# Power_Regulators_Digital_4.net
KiCad netlist of a schematic drawn in Altium Designer
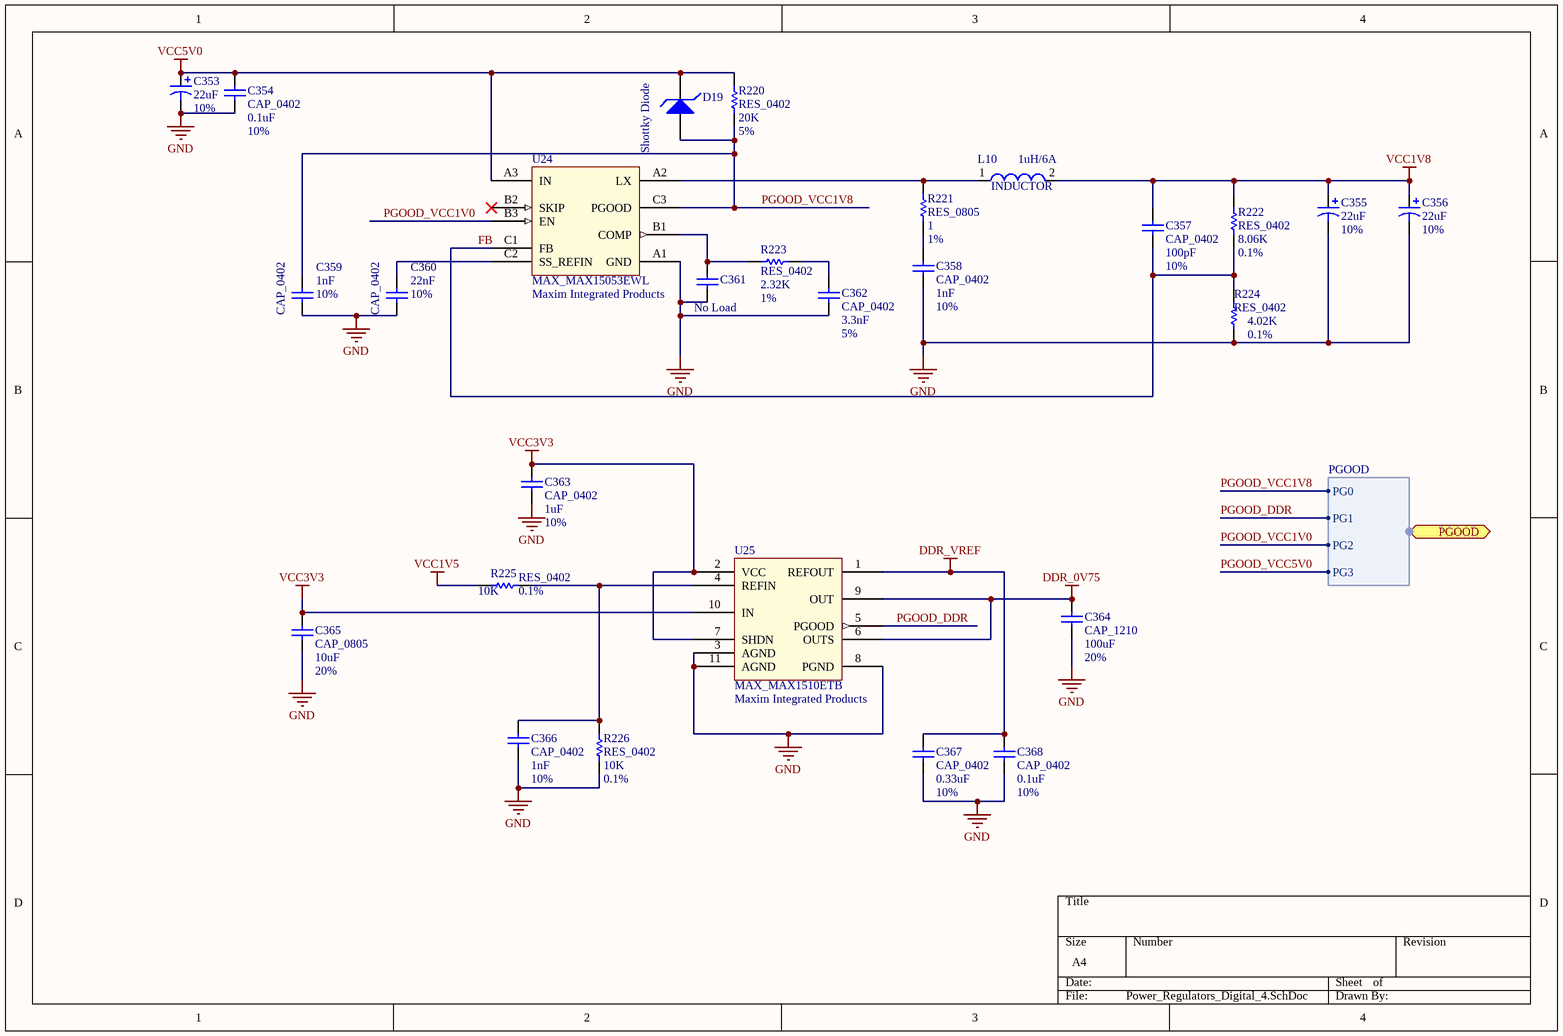
[diagram p0: Power_Regulators_Digital_4.SchDoc]

(export (version "E")
  (design (tool "Eeschema 10.0.6"))
  (components
    (comp (ref "C353")
      (value "22uF")
      (footprint "Polarized_CAPC1210(3225)")
      (description "22uF, tantalum, 10% 6.3V, 1210")
      (fields
        (field (name "TOLERANCE") "10%")
        (field (name "PART NUMBER") "TAJB226K006RNJ")
        (field (name "MANUFACTURER") "AVX Corporation")
      )
      (libsource (lib "COMRAD_Database") (part "Cap Pol1"))
    )
    (comp (ref "C354")
      (value "CAP_0402")
      (footprint "CAPC0402(1005)60_N")
      (description "0.1uf, ceramic, 10%, 6.3V, X5R, 0402")
      (fields
        (field (name "ALTIUM_VALUE") "0.1uF")
        (field (name "TOLERANCE") "10%")
        (field (name "PART NUMBER") "C1005X5R0J104K")
        (field (name "MANUFACTURER") "TDK Corporation")
      )
      (libsource (lib "COMRAD_Database") (part "CAP_0402"))
    )
    (comp (ref "C355")
      (value "22uF")
      (footprint "Polarized_CAPC1210(3225)")
      (description "22uF, tantalum, 10% 6.3V, 1210")
      (fields
        (field (name "TOLERANCE") "10%")
        (field (name "PART NUMBER") "TAJB226K006RNJ")
        (field (name "MANUFACTURER") "AVX Corporation")
      )
      (libsource (lib "COMRAD_Database") (part "Cap Pol1"))
    )
    (comp (ref "C356")
      (value "22uF")
      (footprint "Polarized_CAPC1210(3225)")
      (description "22uF, tantalum, 10% 6.3V, 1210")
      (fields
        (field (name "TOLERANCE") "10%")
        (field (name "PART NUMBER") "TAJB226K006RNJ")
        (field (name "MANUFACTURER") "AVX Corporation")
      )
      (libsource (lib "COMRAD_Database") (part "Cap Pol1"))
    )
    (comp (ref "C357")
      (value "CAP_0402")
      (footprint "CAPC0402(1005)60_N")
      (description "100pF, ceramic, 10% 6.3V X7R, 0402")
      (fields
        (field (name "ALTIUM_VALUE") "100pF")
        (field (name "TOLERANCE") "10%")
        (field (name "PART NUMBER") "04026C101KAT2A")
        (field (name "MANUFACTURER") "AVX Corporation")
      )
      (libsource (lib "COMRAD_Database") (part "CAP_0402"))
    )
    (comp (ref "C358")
      (value "CAP_0402")
      (footprint "CAPC0402(1005)60_N")
      (description "1000pF, ceramic, 10% 25V X7R, 0402")
      (fields
        (field (name "ALTIUM_VALUE") "1nF")
        (field (name "TOLERANCE") "10%")
        (field (name "PART NUMBER") "ECJ-0EB1E102K")
        (field (name "MANUFACTURER") "Panasonic - ECG")
      )
      (libsource (lib "COMRAD_Database") (part "CAP_0402"))
    )
    (comp (ref "C359")
      (value "CAP_0402")
      (footprint "CAPC0402(1005)60_N")
      (description "1000pF, ceramic, 10% 25V X7R, 0402")
      (fields
        (field (name "ALTIUM_VALUE") "1nF")
        (field (name "TOLERANCE") "10%")
        (field (name "PART NUMBER") "ECJ-0EB1E102K")
        (field (name "MANUFACTURER") "Panasonic - ECG")
      )
      (libsource (lib "COMRAD_Database") (part "CAP_0402"))
    )
    (comp (ref "C360")
      (value "CAP_0402")
      (footprint "CAPC0402(1005)60_N")
      (description "0.022uF, ceramic, 10%, 16V, X7R, 0402")
      (fields
        (field (name "ALTIUM_VALUE") "22nF")
        (field (name "TOLERANCE") "10%")
        (field (name "PART NUMBER") "0402YC223KAT2A")
        (field (name "MANUFACTURER") "AVX Corporation")
      )
      (libsource (lib "COMRAD_Database") (part "CAP_0402"))
    )
    (comp (ref "C361")
      (value "No Load")
      (footprint "CAPC0201(0603)33_N:CAPC0201(0603)33_N")
      (description "Generic Capacitor")
      (fields (field (name "Comment") "CAP_0201"))
      (libsource (lib "COMRAD_Database") (part "CAP_0201"))
    )
    (comp (ref "C362")
      (value "CAP_0402")
      (footprint "CAPC0402(1005)60_N")
      (description "3300pF, ceramic 5% 10V, 0402")
      (fields
        (field (name "ALTIUM_VALUE") "3.3nF")
        (field (name "TOLERANCE") "5%")
        (field (name "PART NUMBER") "LMK105SD332JV-F")
        (field (name "MANUFACTURER") "Taiyo Yuden")
      )
      (libsource (lib "COMRAD_Database") (part "CAP_0402"))
    )
    (comp (ref "C363")
      (value "CAP_0402")
      (footprint "CAPC0402(1005)60_N")
      (description "1uF, ceramic, 10%, 6.3V, X5R, 0402")
      (fields
        (field (name "ALTIUM_VALUE") "1uF")
        (field (name "TOLERANCE") "10%")
        (field (name "PART NUMBER") "C1005X5R0J105K")
        (field (name "MANUFACTURER") "TDK Corporation")
      )
      (libsource (lib "COMRAD_Database") (part "CAP_0402"))
    )
    (comp (ref "C364")
      (value "CAP_1210")
      (footprint "CAPC1210(3225)100_N")
      (description "100uF, ceramic, 20% 6.3V X5R, 1210")
      (fields
        (field (name "ALTIUM_VALUE") "100uF")
        (field (name "TOLERANCE") "20%")
        (field (name "PART NUMBER") "GRM32ER60J107ME20L")
        (field (name "MANUFACTURER") "Murata Electronics North America")
      )
      (libsource (lib "COMRAD_Database") (part "CAP_1210"))
    )
    (comp (ref "C365")
      (value "CAP_0805")
      (footprint "CAPC0805(2012)75_N")
      (description "10uF, ceramic, 20%, 6.3V, X5R 0805")
      (fields
        (field (name "ALTIUM_VALUE") "10uF")
        (field (name "TOLERANCE") "20%")
        (field (name "PART NUMBER") "ECJ-2FB0J106M")
        (field (name "MANUFACTURER") "Panasonic - ECG")
      )
      (libsource (lib "COMRAD_Database") (part "CAP_0805"))
    )
    (comp (ref "C366")
      (value "CAP_0402")
      (footprint "CAPC0402(1005)60_N")
      (description "1000pF, ceramic, 10% 25V X7R, 0402")
      (fields
        (field (name "ALTIUM_VALUE") "1nF")
        (field (name "TOLERANCE") "10%")
        (field (name "PART NUMBER") "ECJ-0EB1E102K")
        (field (name "MANUFACTURER") "Panasonic - ECG")
      )
      (libsource (lib "COMRAD_Database") (part "CAP_0402"))
    )
    (comp (ref "C367")
      (value "CAP_0402")
      (footprint "CAPC0402(1005)60_N")
      (description "0.33uF, ceramic, 10% 16V X5R, 0402")
      (fields
        (field (name "ALTIUM_VALUE") "0.33uF")
        (field (name "TOLERANCE") "10%")
        (field (name "PART NUMBER") "C1005X5R1C334K")
        (field (name "MANUFACTURER") "TDK Corporation")
      )
      (libsource (lib "COMRAD_Database") (part "CAP_0402"))
    )
    (comp (ref "C368")
      (value "CAP_0402")
      (footprint "CAPC0402(1005)60_N")
      (description "0.1uf, ceramic, 10%, 6.3V, X5R, 0402")
      (fields
        (field (name "ALTIUM_VALUE") "0.1uF")
        (field (name "TOLERANCE") "10%")
        (field (name "PART NUMBER") "C1005X5R0J104K")
        (field (name "MANUFACTURER") "TDK Corporation")
      )
      (libsource (lib "COMRAD_Database") (part "CAP_0402"))
    )
    (comp (ref "D19")
      (value "Shottky Diode")
      (footprint "SchottkyDiode_RB751S40_2-PIN")
      (description "RB751S40, 40V 30mA schottky, SOD523F")
      (fields (field (name "PART NUMBER") "RB751S40") (field (name "MANUFACTURER") "FAIRCHILD SEMICONDUCTOR"))
      (libsource (lib "COMRAD_Database") (part "ShottkyDiode"))
    )
    (comp (ref "L10")
      (value "INDUCTOR")
      (footprint "Inductor_SRN6045-Series_2-PIN")
      (description "SRN6045-1R0Y, 1uH 4.2A-8.5A, CDRH6D38")
      (fields
        (field (name "ALTIUM_VALUE") "1uH/6A")
        (field (name "PART NUMBER") "SRN6045-1R0Y")
        (field (name "MANUFACTURER") "Bourns")
      )
      (libsource (lib "COMRAD_Database") (part "INDUCTOR"))
    )
    (comp (ref "R220")
      (value "RES_0402")
      (footprint "RESC0402(1005)_N")
      (description "20K ohm, 5%, 1/16W, 0402")
      (fields
        (field (name "ALTIUM_VALUE") "20K")
        (field (name "TOLERANCE") "5%")
        (field (name "PART NUMBER") "ERJ-2GEJ203X")
        (field (name "MANUFACTURER") "Panasonic - ECG")
      )
      (libsource (lib "COMRAD_Database") (part "RES_0402"))
    )
    (comp (ref "R221")
      (value "RES_0805")
      (footprint "RESC0805(2012)_N")
      (description "1 ohm, 1% 1/4W, 0805")
      (fields
        (field (name "ALTIUM_VALUE") "1")
        (field (name "TOLERANCE") "1%")
        (field (name "PART NUMBER") "MCR10EZHFL1R00")
        (field (name "MANUFACTURER") "ROHM")
      )
      (libsource (lib "COMRAD_Database") (part "RES_0805"))
    )
    (comp (ref "R222")
      (value "RES_0402")
      (footprint "RESC0402(1005)_N")
      (description "8.06K ohm, 0.1% 1/16W, 0402")
      (fields
        (field (name "ALTIUM_VALUE") "8.06K")
        (field (name "TOLERANCE") "0.1%")
        (field (name "PART NUMBER") "2-1879215-9")
        (field (name "MANUFACTURER") "TE Connectivity")
      )
      (libsource (lib "COMRAD_Database") (part "RES_0402"))
    )
    (comp (ref "R223")
      (value "RES_0402")
      (footprint "RESC0402(1005)_N")
      (description "2.32K ohm, 1% 1/16W, 0402")
      (fields
        (field (name "ALTIUM_VALUE") "2.32K")
        (field (name "TOLERANCE") "1%")
        (field (name "PART NUMBER") "ERJ-2RKF2321X")
        (field (name "MANUFACTURER") "Panasonic - ECG")
      )
      (libsource (lib "COMRAD_Database") (part "RES_0402"))
    )
    (comp (ref "R224")
      (value "RES_0402")
      (footprint "RESC0402(1005)_N")
      (description "4.02K ohm, 0.1% 1/16W, 0402")
      (fields
        (field (name "ALTIUM_VALUE") "4.02K")
        (field (name "TOLERANCE") "0.1%")
        (field (name "PART NUMBER") "RG1005P-4021-B-T5")
        (field (name "MANUFACTURER") "Susumu Co Ltd")
      )
      (libsource (lib "COMRAD_Database") (part "RES_0402"))
    )
    (comp (ref "R225")
      (value "RES_0402")
      (footprint "RESC0402(1005)_N")
      (description "10K ohm, 0.1% 1/16W, 0402")
      (fields
        (field (name "ALTIUM_VALUE") "10K")
        (field (name "TOLERANCE") "0.1%")
        (field (name "PART NUMBER") "ERA-2AEB103X")
        (field (name "MANUFACTURER") "Panasonic - ECG")
      )
      (libsource (lib "COMRAD_Database") (part "RES_0402"))
    )
    (comp (ref "R226")
      (value "RES_0402")
      (footprint "RESC0402(1005)_N")
      (description "10K ohm, 0.1% 1/16W, 0402")
      (fields
        (field (name "ALTIUM_VALUE") "10K")
        (field (name "TOLERANCE") "0.1%")
        (field (name "PART NUMBER") "ERA-2AEB103X")
        (field (name "MANUFACTURER") "Panasonic - ECG")
      )
      (libsource (lib "COMRAD_Database") (part "RES_0402"))
    )
    (comp (ref "U24")
      (value "MAX_MAX15053EWL")
      (footprint "MAX_MAX15053EWL_9WLP_W91E1Z+1")
      (description "MAX15053EWL, 2A, Current-Mode Synchronous, Step-Down reg, WLP9")
      (fields
        (field (name "PART NUMBER") "MAX15053EWL+T")
        (field (name "MANUFACTURER") "Maxim Integrated Products")
      )
      (libsource (lib "COMRAD_Database") (part "MAX_MAX15053EWL"))
    )
    (comp (ref "U25")
      (value "MAX_MAX1510ETB")
      (footprint "MAX_MAX1510ETB_10TDFN_T1033+1")
      (description "MAX1510ETB, Low-Voltage, DDR Linear Regulators, DFN10")
      (fields
        (field (name "PART NUMBER") "MAX1510ETB+T")
        (field (name "MANUFACTURER") "Maxim Integrated Products")
      )
      (libsource (lib "COMRAD_Database") (part "MAX_MAX1510ETB"))
    )
  )
  (nets
    (net (code "2") (name "/FB") (class "Default")
      (node (ref "C357") (pin "1") (pinfunction "1_1") (pintype "passive"))
      (node (ref "R222") (pin "1") (pinfunction "1_1") (pintype "passive"))
      (node (ref "R224") (pin "2") (pinfunction "2_2") (pintype "passive"))
      (node (ref "U24") (pin "C1") (pinfunction "FB_C1") (pintype "power_in"))
    )
    (net (code "3") (name "/PGOOD_DDR") (class "Default")
      (node (ref "U25") (pin "5") (pinfunction "PGOOD_5") (pintype "output"))
    )
    (net (code "4") (name "/PGOOD_VCC1V0") (class "Default")
      (node (ref "U24") (pin "B3") (pinfunction "EN_B3") (pintype "input"))
    )
    (net (code "5") (name "/PGOOD_VCC1V8") (class "Default")
      (node (ref "C359") (pin "2") (pinfunction "2_2") (pintype "passive"))
      (node (ref "D19") (pin "2") (pinfunction "A_2") (pintype "passive"))
      (node (ref "R220") (pin "1") (pinfunction "1_1") (pintype "passive"))
      (node (ref "U24") (pin "C3") (pinfunction "PGOOD_C3") (pintype "passive"))
    )
    (net (code "8") (name "DDR_0V75") (class "Default")
      (node (ref "C364") (pin "2") (pinfunction "2_2") (pintype "passive"))
      (node (ref "U25") (pin "6") (pinfunction "OUTS_6") (pintype "passive"))
      (node (ref "U25") (pin "9") (pinfunction "OUT_9") (pintype "passive"))
    )
    (net (code "9") (name "DDR_VREF") (class "Default")
      (node (ref "C367") (pin "2") (pinfunction "2_2") (pintype "passive"))
      (node (ref "C368") (pin "2") (pinfunction "2_2") (pintype "passive"))
      (node (ref "U25") (pin "1") (pinfunction "REFOUT_1") (pintype "power_in"))
    )
    (net (code "10") (name "GND") (class "Default")
      (node (ref "C353") (pin "2") (pinfunction "2_2") (pintype "passive"))
      (node (ref "C354") (pin "1") (pinfunction "1_1") (pintype "passive"))
      (node (ref "C355") (pin "2") (pinfunction "2_2") (pintype "passive"))
      (node (ref "C356") (pin "2") (pinfunction "2_2") (pintype "passive"))
      (node (ref "C358") (pin "1") (pinfunction "1_1") (pintype "passive"))
      (node (ref "C359") (pin "1") (pinfunction "1_1") (pintype "passive"))
      (node (ref "C360") (pin "1") (pinfunction "1_1") (pintype "passive"))
      (node (ref "C361") (pin "1") (pinfunction "1_1") (pintype "passive"))
      (node (ref "C362") (pin "1") (pinfunction "1_1") (pintype "passive"))
      (node (ref "C363") (pin "1") (pinfunction "1_1") (pintype "passive"))
      (node (ref "C364") (pin "1") (pinfunction "1_1") (pintype "passive"))
      (node (ref "C365") (pin "1") (pinfunction "1_1") (pintype "passive"))
      (node (ref "C366") (pin "1") (pinfunction "1_1") (pintype "passive"))
      (node (ref "C367") (pin "1") (pinfunction "1_1") (pintype "passive"))
      (node (ref "C368") (pin "1") (pinfunction "1_1") (pintype "passive"))
      (node (ref "R224") (pin "1") (pinfunction "1_1") (pintype "passive"))
      (node (ref "R226") (pin "1") (pinfunction "1_1") (pintype "passive"))
      (node (ref "U24") (pin "A1") (pinfunction "GND_A1") (pintype "power_in"))
      (node (ref "U25") (pin "11") (pinfunction "AGND_11") (pintype "power_in"))
      (node (ref "U25") (pin "3") (pinfunction "AGND_3") (pintype "power_in"))
      (node (ref "U25") (pin "8") (pinfunction "PGND_8") (pintype "power_in"))
    )
    (net (code "11") (name "Net-(C358-Pad2)") (class "Default")
      (node (ref "C358") (pin "2") (pinfunction "2_2") (pintype "passive"))
      (node (ref "R221") (pin "1") (pinfunction "1_1") (pintype "passive"))
    )
    (net (code "12") (name "Net-(C362-Pad2)") (class "Default")
      (node (ref "C362") (pin "2") (pinfunction "2_2") (pintype "passive"))
      (node (ref "R223") (pin "2") (pinfunction "2_2") (pintype "passive"))
    )
    (net (code "13") (name "Net-(U24-COMP)") (class "Default")
      (node (ref "C361") (pin "2") (pinfunction "2_2") (pintype "passive"))
      (node (ref "R223") (pin "1") (pinfunction "1_1") (pintype "passive"))
      (node (ref "U24") (pin "B1") (pinfunction "COMP_B1") (pintype "output"))
    )
    (net (code "14") (name "Net-(U24-LX)") (class "Default")
      (node (ref "L10") (pin "1") (pinfunction "1_1") (pintype "passive"))
      (node (ref "R221") (pin "2") (pinfunction "2_2") (pintype "passive"))
      (node (ref "U24") (pin "A2") (pinfunction "LX_A2") (pintype "power_in"))
    )
    (net (code "15") (name "Net-(U24-SS_REFIN)") (class "Default")
      (node (ref "C360") (pin "2") (pinfunction "2_2") (pintype "passive"))
      (node (ref "U24") (pin "C2") (pinfunction "SS_REFIN_C2") (pintype "power_in"))
    )
    (net (code "16") (name "Net-(U25-REFIN)") (class "Default")
      (node (ref "C366") (pin "2") (pinfunction "2_2") (pintype "passive"))
      (node (ref "R225") (pin "2") (pinfunction "2_2") (pintype "passive"))
      (node (ref "R226") (pin "2") (pinfunction "2_2") (pintype "passive"))
      (node (ref "U25") (pin "4") (pinfunction "REFIN_4") (pintype "power_in"))
    )
    (net (code "17") (name "VCC1V5") (class "Default")
      (node (ref "R225") (pin "1") (pinfunction "1_1") (pintype "passive"))
    )
    (net (code "18") (name "VCC1V8") (class "Default")
      (node (ref "C355") (pin "1") (pinfunction "1_1") (pintype "passive"))
      (node (ref "C356") (pin "1") (pinfunction "1_1") (pintype "passive"))
      (node (ref "C357") (pin "2") (pinfunction "2_2") (pintype "passive"))
      (node (ref "L10") (pin "2") (pinfunction "2_2") (pintype "passive"))
      (node (ref "R222") (pin "2") (pinfunction "2_2") (pintype "passive"))
    )
    (net (code "19") (name "VCC3V3") (class "Default")
      (node (ref "C363") (pin "2") (pinfunction "2_2") (pintype "passive"))
      (node (ref "C365") (pin "2") (pinfunction "2_2") (pintype "passive"))
      (node (ref "U25") (pin "10") (pinfunction "IN_10") (pintype "power_in"))
      (node (ref "U25") (pin "2") (pinfunction "VCC_2") (pintype "power_in"))
      (node (ref "U25") (pin "7") (pinfunction "SHDN_7") (pintype "power_in"))
    )
    (net (code "20") (name "VCC5V0") (class "Default")
      (node (ref "C353") (pin "1") (pinfunction "1_1") (pintype "passive"))
      (node (ref "C354") (pin "2") (pinfunction "2_2") (pintype "passive"))
      (node (ref "D19") (pin "1") (pinfunction "K_1") (pintype "passive"))
      (node (ref "R220") (pin "2") (pinfunction "2_2") (pintype "passive"))
      (node (ref "U24") (pin "A3") (pinfunction "IN_A3") (pintype "power_in"))
    )
    (net (code "21") (name "unconnected-(U24-SKIP-PadB2)") (class "Default")
      (node (ref "U24") (pin "B2") (pinfunction "SKIP_B2") (pintype "input+no_connect"))
    )
  )
)
